# SchlapphutProjekt_v1_0.net
KiCad netlist of a schematic drawn in EAGLE
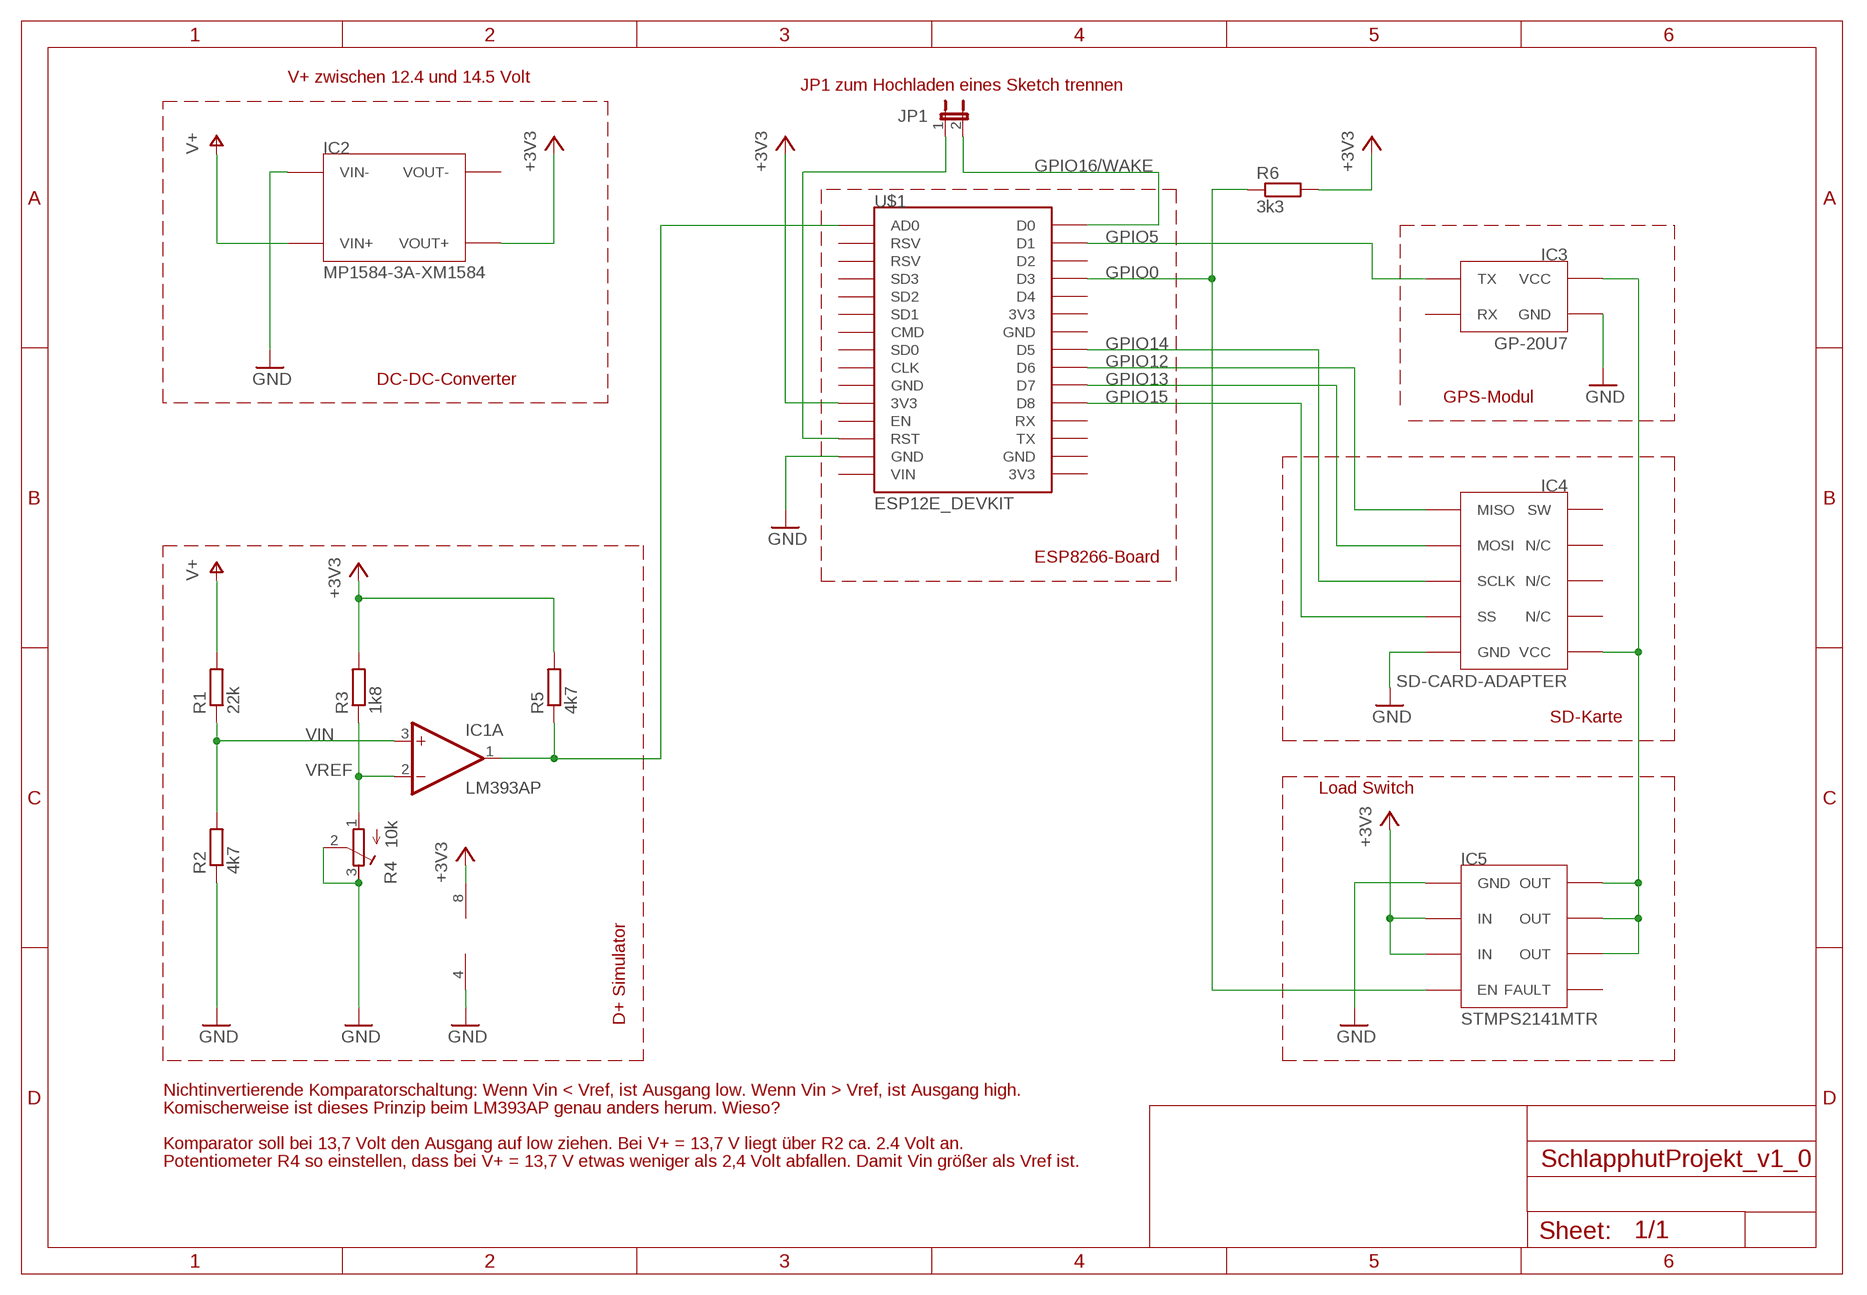
[diagram p0: schematic, sheet 1]

(export (version "E")
  (design (tool "Eeschema 10.0.6"))
  (components
    (comp (ref "IC1")
      (value "LM393AP")
      (footprint "eagle-import:DIL08")
      (libsource (lib "eagle-import") (part "LM393N"))
    )
    (comp (ref "IC2")
      (value "MP1584-3A-XM1584")
      (footprint "eagle-import:KA278R33CTU")
      (libsource (lib "eagle-import") (part "MP1584-3A-XM1584"))
    )
    (comp (ref "IC3")
      (value "GP-20U7")
      (footprint "eagle-import:KA278R33CTU")
      (libsource (lib "eagle-import") (part "GY-GPS6MV2"))
    )
    (comp (ref "IC4")
      (value "SD-CARD-ADAPTER")
      (footprint "eagle-import:SD-CARD-ADAPTER")
      (libsource (lib "eagle-import") (part "SD-CARD-ADAPTER"))
    )
    (comp (ref "IC5")
      (value "STMPS2141MTR")
      (footprint "eagle-import:STMPS2141MTR")
      (libsource (lib "eagle-import") (part "STMPS2141MTR"))
    )
    (comp (ref "JP1")
      (value "JP1 zum Hochladen eines Sketch trennen")
      (footprint "eagle-import:JP1")
      (libsource (lib "eagle-import") (part "JP1E"))
    )
    (comp (ref "R1")
      (value "22k")
      (footprint "eagle-import:0207_12")
      (libsource (lib "eagle-import") (part "R-EU_0207/12"))
    )
    (comp (ref "R2")
      (value "4k7")
      (footprint "eagle-import:0207_12")
      (libsource (lib "eagle-import") (part "R-EU_0207/12"))
    )
    (comp (ref "R3")
      (value "1k8")
      (footprint "eagle-import:0207_12")
      (libsource (lib "eagle-import") (part "R-EU_0207/12"))
    )
    (comp (ref "R4")
      (value "10k")
      (footprint "eagle-import:RTRIM64Z")
      (libsource (lib "eagle-import") (part "R-TRIMM64Z"))
    )
    (comp (ref "R5")
      (value "4k7")
      (footprint "eagle-import:0207_12")
      (libsource (lib "eagle-import") (part "R-EU_0207/12"))
    )
    (comp (ref "R6")
      (value "3k3")
      (footprint "eagle-import:0207_12")
      (libsource (lib "eagle-import") (part "R-EU_0207/12"))
    )
    (comp (ref "U$1")
      (value "ESP12E_DEVKIT")
      (footprint "eagle-import:ESP12E_DEVKIT")
      (libsource (lib "eagle-import") (part "ESP12E_DEVKIT"))
    )
  )
  (nets
    (net (code "1") (name "+3V3") (class "Default")
      (node (ref "IC1") (pin "8") (pinfunction "V+_8") (pintype "power_in"))
      (node (ref "IC2") (pin "3") (pinfunction "VOUT+_3") (pintype "power_in"))
      (node (ref "IC5") (pin "P$4") (pinfunction "IN_P$4") (pintype "input"))
      (node (ref "IC5") (pin "P$5") (pinfunction "IN_P$5") (pintype "input"))
      (node (ref "R3") (pin "2") (pinfunction "2_2") (pintype "passive"))
      (node (ref "R5") (pin "2") (pinfunction "2_2") (pintype "passive"))
      (node (ref "R6") (pin "2") (pinfunction "2_2") (pintype "passive"))
      (node (ref "U$1") (pin "3V3@0") (pinfunction "3V3_3V3@0") (pintype "bidirectional"))
    )
    (net (code "2") (name "/GPIO0") (class "Default")
      (node (ref "IC5") (pin "P$1") (pinfunction "EN_P$1") (pintype "bidirectional"))
      (node (ref "R6") (pin "1") (pinfunction "1_1") (pintype "passive"))
      (node (ref "U$1") (pin "D3") (pinfunction "D3_D3") (pintype "bidirectional"))
    )
    (net (code "3") (name "/GPIO5") (class "Default")
      (node (ref "IC3") (pin "3") (pinfunction "TX_3") (pintype "bidirectional"))
      (node (ref "U$1") (pin "D1") (pinfunction "D1_D1") (pintype "bidirectional"))
    )
    (net (code "4") (name "/GPIO12") (class "Default")
      (node (ref "IC4") (pin "10") (pinfunction "MISO_10") (pintype "bidirectional"))
      (node (ref "U$1") (pin "D6") (pinfunction "D6_D6") (pintype "bidirectional"))
    )
    (net (code "5") (name "/GPIO13") (class "Default")
      (node (ref "IC4") (pin "9") (pinfunction "MOSI_9") (pintype "bidirectional"))
      (node (ref "U$1") (pin "D7") (pinfunction "D7_D7") (pintype "bidirectional"))
    )
    (net (code "6") (name "/GPIO14") (class "Default")
      (node (ref "IC4") (pin "8") (pinfunction "SCLK_8") (pintype "bidirectional"))
      (node (ref "U$1") (pin "D5") (pinfunction "D5_D5") (pintype "bidirectional"))
    )
    (net (code "7") (name "/GPIO15") (class "Default")
      (node (ref "IC4") (pin "7") (pinfunction "SS_7") (pintype "bidirectional"))
      (node (ref "U$1") (pin "D8") (pinfunction "D8_D8") (pintype "bidirectional"))
    )
    (net (code "8") (name "/GPIO16{slash}WAKE") (class "Default")
      (node (ref "JP1") (pin "2") (pinfunction "2_2") (pintype "passive"))
      (node (ref "U$1") (pin "D0") (pinfunction "D0_D0") (pintype "bidirectional"))
    )
    (net (code "9") (name "/VIN") (class "Default")
      (node (ref "IC1") (pin "3") (pinfunction "+IN_3") (pintype "input"))
      (node (ref "R1") (pin "1") (pinfunction "1_1") (pintype "passive"))
      (node (ref "R2") (pin "2") (pinfunction "2_2") (pintype "passive"))
    )
    (net (code "10") (name "/VOUT-") (class "Default")
      (node (ref "IC2") (pin "4") (pinfunction "VOUT-_4") (pintype "power_in"))
    )
    (net (code "11") (name "/VREF") (class "Default")
      (node (ref "IC1") (pin "2") (pinfunction "-IN_2") (pintype "input"))
      (node (ref "R3") (pin "1") (pinfunction "1_1") (pintype "passive"))
      (node (ref "R4") (pin "1") (pinfunction "A_1") (pintype "passive"))
    )
    (net (code "12") (name "GND") (class "Default")
      (node (ref "IC1") (pin "4") (pinfunction "V-_4") (pintype "power_in"))
      (node (ref "IC2") (pin "2") (pinfunction "VIN-_2") (pintype "power_in"))
      (node (ref "IC3") (pin "4") (pinfunction "GND_4") (pintype "power_in"))
      (node (ref "IC4") (pin "6") (pinfunction "GND_6") (pintype "bidirectional"))
      (node (ref "IC5") (pin "P$3") (pinfunction "GND_P$3") (pintype "bidirectional"))
      (node (ref "R2") (pin "1") (pinfunction "1_1") (pintype "passive"))
      (node (ref "R4") (pin "2") (pinfunction "S_2") (pintype "passive"))
      (node (ref "R4") (pin "3") (pinfunction "E_3") (pintype "passive"))
      (node (ref "U$1") (pin "GND@1") (pinfunction "GND_GND@1") (pintype "bidirectional"))
    )
    (net (code "13") (name "Net-(IC1A-OUT)") (class "Default")
      (node (ref "IC1") (pin "1") (pinfunction "OUT_1") (pintype "output"))
      (node (ref "R5") (pin "1") (pinfunction "1_1") (pintype "passive"))
      (node (ref "U$1") (pin "AD0") (pinfunction "AD0_AD0") (pintype "bidirectional"))
    )
    (net (code "14") (name "Net-(IC3-VCC)") (class "Default")
      (node (ref "IC3") (pin "1") (pinfunction "VCC_1") (pintype "power_in"))
      (node (ref "IC4") (pin "5") (pinfunction "VCC_5") (pintype "bidirectional"))
      (node (ref "IC5") (pin "P$6") (pinfunction "OUT_P$6") (pintype "output"))
      (node (ref "IC5") (pin "P$7") (pinfunction "OUT_P$7") (pintype "output"))
      (node (ref "IC5") (pin "P$8") (pinfunction "OUT_P$8") (pintype "output"))
    )
    (net (code "15") (name "Net-(JP1-Pad1)") (class "Default")
      (node (ref "JP1") (pin "1") (pinfunction "1_1") (pintype "passive"))
      (node (ref "U$1") (pin "RST") (pinfunction "RST_RST") (pintype "bidirectional"))
    )
    (net (code "16") (name "V+") (class "Default")
      (node (ref "IC2") (pin "1") (pinfunction "VIN+_1") (pintype "power_in"))
      (node (ref "R1") (pin "2") (pinfunction "2_2") (pintype "passive"))
    )
    (net (code "17") (name "unconnected-(IC3-RX-Pad2)") (class "Default")
      (node (ref "IC3") (pin "2") (pinfunction "RX_2") (pintype "bidirectional"))
    )
    (net (code "18") (name "unconnected-(IC4-N{slash}C-Pad2)") (class "Default")
      (node (ref "IC4") (pin "2") (pinfunction "N/C_2") (pintype "bidirectional"))
    )
    (net (code "19") (name "unconnected-(IC4-N{slash}C-Pad3)") (class "Default")
      (node (ref "IC4") (pin "3") (pinfunction "N/C_3") (pintype "no_connect"))
    )
    (net (code "20") (name "unconnected-(IC4-N{slash}C-Pad4)") (class "Default")
      (node (ref "IC4") (pin "4") (pinfunction "N/C_4") (pintype "bidirectional"))
    )
    (net (code "21") (name "unconnected-(IC4-SW-Pad1)") (class "Default")
      (node (ref "IC4") (pin "1") (pinfunction "SW_1") (pintype "bidirectional"))
    )
    (net (code "22") (name "unconnected-(IC5-FAULT-PadP$2)") (class "Default")
      (node (ref "IC5") (pin "P$2") (pinfunction "FAULT_P$2") (pintype "bidirectional"))
    )
    (net (code "23") (name "unconnected-(U$1-3V3-Pad3V3@1)") (class "Default")
      (node (ref "U$1") (pin "3V3@1") (pinfunction "3V3_3V3@1") (pintype "bidirectional"))
    )
    (net (code "24") (name "unconnected-(U$1-3V3-Pad3V3@2)") (class "Default")
      (node (ref "U$1") (pin "3V3@2") (pinfunction "3V3_3V3@2") (pintype "bidirectional"))
    )
    (net (code "25") (name "unconnected-(U$1-GND-PadGND@0)") (class "Default")
      (node (ref "U$1") (pin "GND@0") (pinfunction "GND_GND@0") (pintype "bidirectional"))
    )
    (net (code "26") (name "unconnected-(U$1-GND-PadGND@2)") (class "Default")
      (node (ref "U$1") (pin "GND@2") (pinfunction "GND_GND@2") (pintype "bidirectional"))
    )
    (net (code "27") (name "unconnected-(U$1-GND-PadGND@3)") (class "Default")
      (node (ref "U$1") (pin "GND@3") (pinfunction "GND_GND@3") (pintype "bidirectional"))
    )
    (net (code "28") (name "unconnected-(U$1-PadCLK)") (class "Default")
      (node (ref "U$1") (pin "CLK") (pinfunction "CLK_CLK") (pintype "bidirectional"))
    )
    (net (code "29") (name "unconnected-(U$1-PadCMD)") (class "Default")
      (node (ref "U$1") (pin "CMD") (pinfunction "CMD_CMD") (pintype "bidirectional"))
    )
    (net (code "30") (name "unconnected-(U$1-PadD2)") (class "Default")
      (node (ref "U$1") (pin "D2") (pinfunction "D2_D2") (pintype "bidirectional"))
    )
    (net (code "31") (name "unconnected-(U$1-PadD4)") (class "Default")
      (node (ref "U$1") (pin "D4") (pinfunction "D4_D4") (pintype "bidirectional"))
    )
    (net (code "32") (name "unconnected-(U$1-PadEN)") (class "Default")
      (node (ref "U$1") (pin "EN") (pinfunction "EN_EN") (pintype "bidirectional"))
    )
    (net (code "33") (name "unconnected-(U$1-PadRX)") (class "Default")
      (node (ref "U$1") (pin "RX") (pinfunction "RX_RX") (pintype "bidirectional"))
    )
    (net (code "34") (name "unconnected-(U$1-PadSD0)") (class "Default")
      (node (ref "U$1") (pin "SD0") (pinfunction "SD0_SD0") (pintype "bidirectional"))
    )
    (net (code "35") (name "unconnected-(U$1-PadSD1)") (class "Default")
      (node (ref "U$1") (pin "SD1") (pinfunction "SD1_SD1") (pintype "bidirectional"))
    )
    (net (code "36") (name "unconnected-(U$1-PadSD2)") (class "Default")
      (node (ref "U$1") (pin "SD2") (pinfunction "SD2_SD2") (pintype "bidirectional"))
    )
    (net (code "37") (name "unconnected-(U$1-PadSD3)") (class "Default")
      (node (ref "U$1") (pin "SD3") (pinfunction "SD3_SD3") (pintype "bidirectional"))
    )
    (net (code "38") (name "unconnected-(U$1-PadTX)") (class "Default")
      (node (ref "U$1") (pin "TX") (pinfunction "TX_TX") (pintype "bidirectional"))
    )
    (net (code "39") (name "unconnected-(U$1-PadVIN)") (class "Default")
      (node (ref "U$1") (pin "VIN") (pinfunction "VIN_VIN") (pintype "bidirectional"))
    )
    (net (code "40") (name "unconnected-(U$1-RSV-PadRSV@0)") (class "Default")
      (node (ref "U$1") (pin "RSV@0") (pinfunction "RSV_RSV@0") (pintype "bidirectional"))
    )
    (net (code "41") (name "unconnected-(U$1-RSV-PadRSV@1)") (class "Default")
      (node (ref "U$1") (pin "RSV@1") (pinfunction "RSV_RSV@1") (pintype "bidirectional"))
    )
  )
)
